# TC377TP_1.net
KiCad netlist of a schematic drawn in Altium Designer
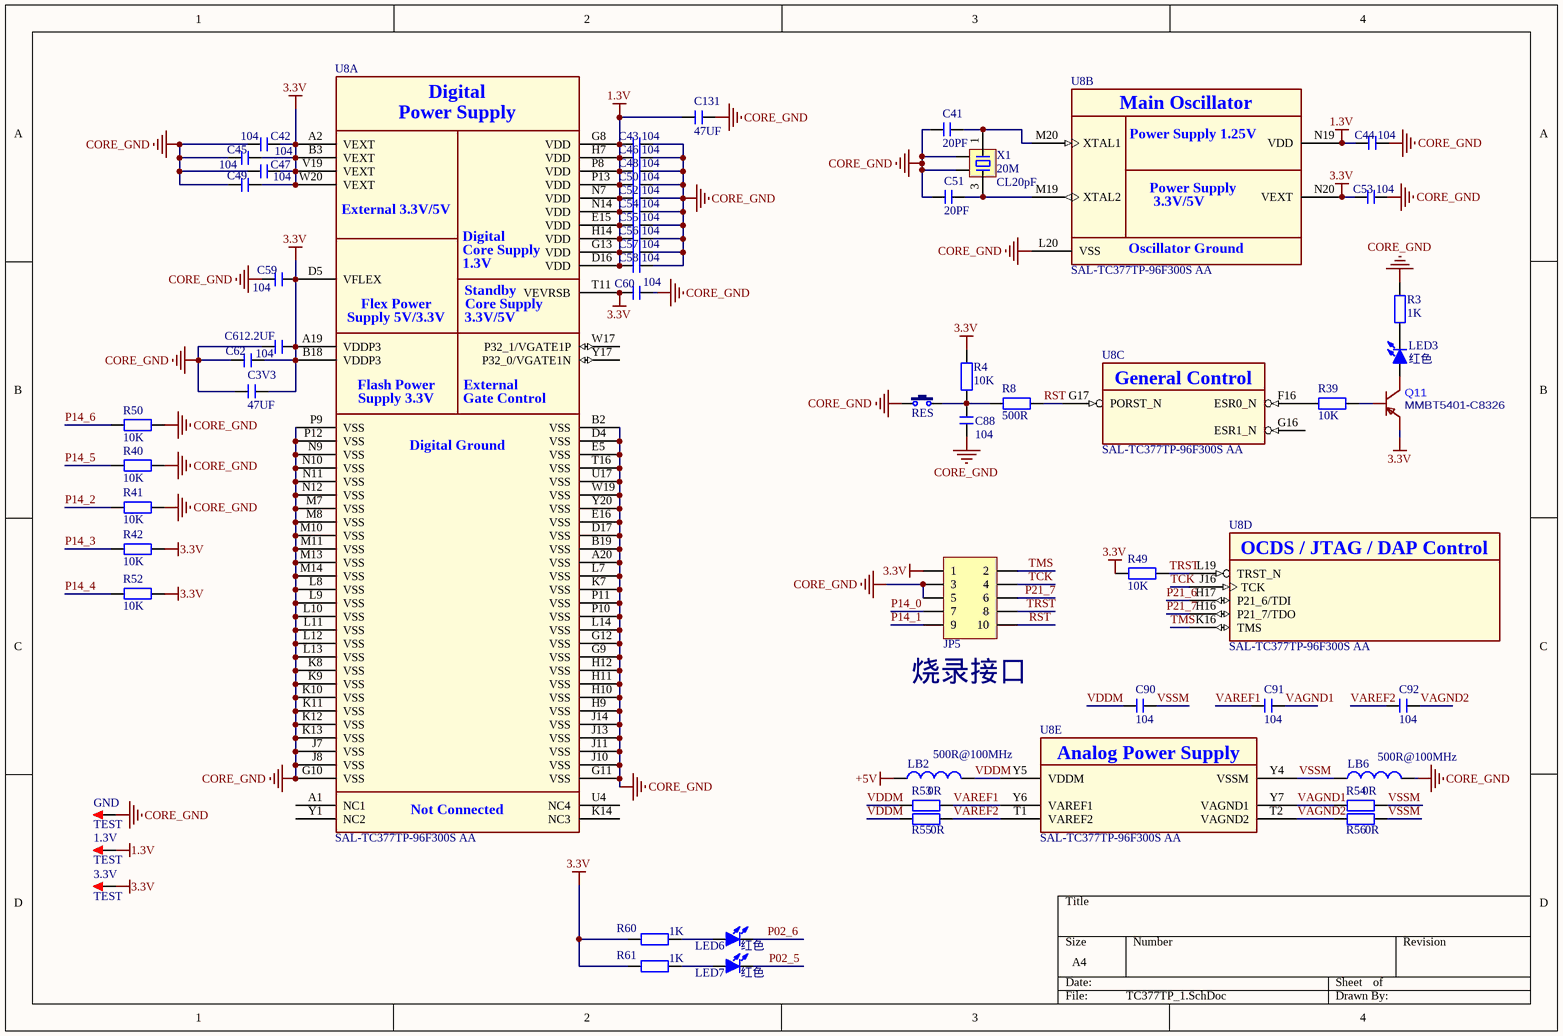
[diagram p0: TC377TP_1.SchDoc]

(export (version "E")
  (design (tool "Eeschema 10.0.6"))
  (components
    (comp (ref "1.3V")
      (value "TEST")
      (footprint "TEST 1.6")
      (description "测试点")
      (fields (field (name "版权归属") "源创客"))
      (libsource (lib "15.1 - 未分类器件") (part "TEST"))
    )
    (comp (ref "3.3V")
      (value "TEST")
      (footprint "TEST 1.6")
      (description "测试点")
      (fields (field (name "版权归属") "源创客"))
      (libsource (lib "15.1 - 未分类器件") (part "TEST"))
    )
    (comp (ref "C3V3")
      (value "47UF")
      (footprint "C 0805_L")
      (description "无极性贴片电容")
      (fields (field (name "版权归属") "源创客"))
      (libsource (lib "3.1   - 电阻-电容-电感") (part "C"))
    )
    (comp (ref "C41")
      (value "20PF")
      (footprint "C 0603_L")
      (description "无极性贴片电容")
      (fields (field (name "版权归属") "源创客"))
      (libsource (lib "3.1   - 电阻-电容-电感") (part "C"))
    )
    (comp (ref "C42")
      (value "104")
      (footprint "C 0603_L")
      (description "无极性贴片电容")
      (fields (field (name "版权归属") "源创客"))
      (libsource (lib "3.1   - 电阻-电容-电感") (part "C"))
    )
    (comp (ref "C43")
      (value "104")
      (footprint "C 0603_L")
      (description "无极性贴片电容")
      (fields (field (name "版权归属") "源创客"))
      (libsource (lib "3.1   - 电阻-电容-电感") (part "C"))
    )
    (comp (ref "C44")
      (value "104")
      (footprint "C 0603_L")
      (description "无极性贴片电容")
      (fields (field (name "版权归属") "源创客"))
      (libsource (lib "3.1   - 电阻-电容-电感") (part "C"))
    )
    (comp (ref "C45")
      (value "104")
      (footprint "C 0603_L")
      (description "无极性贴片电容")
      (fields (field (name "版权归属") "源创客"))
      (libsource (lib "3.1   - 电阻-电容-电感") (part "C"))
    )
    (comp (ref "C46")
      (value "104")
      (footprint "C 0603_L")
      (description "无极性贴片电容")
      (fields (field (name "版权归属") "源创客"))
      (libsource (lib "3.1   - 电阻-电容-电感") (part "C"))
    )
    (comp (ref "C47")
      (value "104")
      (footprint "C 0603_L")
      (description "无极性贴片电容")
      (fields (field (name "版权归属") "源创客"))
      (libsource (lib "3.1   - 电阻-电容-电感") (part "C"))
    )
    (comp (ref "C48")
      (value "104")
      (footprint "C 0603_L")
      (description "无极性贴片电容")
      (fields (field (name "版权归属") "源创客"))
      (libsource (lib "3.1   - 电阻-电容-电感") (part "C"))
    )
    (comp (ref "C49")
      (value "104")
      (footprint "C 0603_L")
      (description "无极性贴片电容")
      (fields (field (name "版权归属") "源创客"))
      (libsource (lib "3.1   - 电阻-电容-电感") (part "C"))
    )
    (comp (ref "C50")
      (value "104")
      (footprint "C 0603_L")
      (description "无极性贴片电容")
      (fields (field (name "版权归属") "源创客"))
      (libsource (lib "3.1   - 电阻-电容-电感") (part "C"))
    )
    (comp (ref "C51")
      (value "20PF")
      (footprint "C 0603_L")
      (description "无极性贴片电容")
      (fields (field (name "版权归属") "源创客"))
      (libsource (lib "3.1   - 电阻-电容-电感") (part "C"))
    )
    (comp (ref "C52")
      (value "104")
      (footprint "C 0603_L")
      (description "无极性贴片电容")
      (fields (field (name "版权归属") "源创客"))
      (libsource (lib "3.1   - 电阻-电容-电感") (part "C"))
    )
    (comp (ref "C53")
      (value "104")
      (footprint "C 0603_L")
      (description "无极性贴片电容")
      (fields (field (name "版权归属") "源创客"))
      (libsource (lib "3.1   - 电阻-电容-电感") (part "C"))
    )
    (comp (ref "C54")
      (value "104")
      (footprint "C 0603_L")
      (description "无极性贴片电容")
      (fields (field (name "版权归属") "源创客"))
      (libsource (lib "3.1   - 电阻-电容-电感") (part "C"))
    )
    (comp (ref "C55")
      (value "104")
      (footprint "C 0603_L")
      (description "无极性贴片电容")
      (fields (field (name "版权归属") "源创客"))
      (libsource (lib "3.1   - 电阻-电容-电感") (part "C"))
    )
    (comp (ref "C56")
      (value "104")
      (footprint "C 0603_L")
      (description "无极性贴片电容")
      (fields (field (name "版权归属") "源创客"))
      (libsource (lib "3.1   - 电阻-电容-电感") (part "C"))
    )
    (comp (ref "C57")
      (value "104")
      (footprint "C 0603_L")
      (description "无极性贴片电容")
      (fields (field (name "版权归属") "源创客"))
      (libsource (lib "3.1   - 电阻-电容-电感") (part "C"))
    )
    (comp (ref "C58")
      (value "104")
      (footprint "C 0603_L")
      (description "无极性贴片电容")
      (fields (field (name "版权归属") "源创客"))
      (libsource (lib "3.1   - 电阻-电容-电感") (part "C"))
    )
    (comp (ref "C59")
      (value "104")
      (footprint "C 0603_L")
      (description "无极性贴片电容")
      (fields (field (name "版权归属") "源创客"))
      (libsource (lib "3.1   - 电阻-电容-电感") (part "C"))
    )
    (comp (ref "C60")
      (value "104")
      (footprint "C 0603_L")
      (description "无极性贴片电容")
      (fields (field (name "版权归属") "源创客"))
      (libsource (lib "3.1   - 电阻-电容-电感") (part "C"))
    )
    (comp (ref "C61")
      (value "2.2UF")
      (footprint "C 0603_L")
      (description "无极性贴片电容")
      (fields (field (name "版权归属") "源创客"))
      (libsource (lib "3.1   - 电阻-电容-电感") (part "C"))
    )
    (comp (ref "C62")
      (value "104")
      (footprint "C 0603_L")
      (description "无极性贴片电容")
      (fields (field (name "版权归属") "源创客"))
      (libsource (lib "3.1   - 电阻-电容-电感") (part "C"))
    )
    (comp (ref "C88")
      (value "104")
      (footprint "C 0603_L")
      (description "无极性贴片电容")
      (fields (field (name "版权归属") "源创客"))
      (libsource (lib "3.1   - 电阻-电容-电感") (part "C"))
    )
    (comp (ref "C90")
      (value "104")
      (footprint "C 0603_L")
      (description "无极性贴片电容")
      (fields (field (name "版权归属") "源创客"))
      (libsource (lib "3.1   - 电阻-电容-电感") (part "C"))
    )
    (comp (ref "C91")
      (value "104")
      (footprint "C 0603_L")
      (description "无极性贴片电容")
      (fields (field (name "版权归属") "源创客"))
      (libsource (lib "3.1   - 电阻-电容-电感") (part "C"))
    )
    (comp (ref "C92")
      (value "104")
      (footprint "C 0603_L")
      (description "无极性贴片电容")
      (fields (field (name "版权归属") "源创客"))
      (libsource (lib "3.1   - 电阻-电容-电感") (part "C"))
    )
    (comp (ref "C131")
      (value "47UF")
      (footprint "C 0805_L")
      (description "无极性贴片电容")
      (fields (field (name "版权归属") "源创客"))
      (libsource (lib "3.1   - 电阻-电容-电感") (part "C"))
    )
    (comp (ref "GND")
      (value "TEST")
      (footprint "TEST 1.6")
      (description "测试点")
      (fields (field (name "版权归属") "源创客"))
      (libsource (lib "15.1 - 未分类器件") (part "TEST"))
    )
    (comp (ref "JP5")
      (value "Header 5X2")
      (footprint "IDC2.54-LI-2x5P")
      (description "5*2P接插件")
      (fields (field (name "版权归属") "源创客"))
      (libsource (lib "4.6   - 接插件-脚距2.54") (part "Header 5X2"))
    )
    (comp (ref "LB2")
      (value "500R@100MHz")
      (footprint "FB 0603_L")
      (description "磁珠")
      (fields (field (name "版权归属") "源创客"))
      (libsource (lib "3.1   - 电阻-电容-电感") (part "LB"))
    )
    (comp (ref "LB6")
      (value "500R@100MHz")
      (footprint "FB 0603_L")
      (description "磁珠")
      (fields (field (name "版权归属") "源创客"))
      (libsource (lib "3.1   - 电阻-电容-电感") (part "LB"))
    )
    (comp (ref "LED3")
      (value "红色")
      (footprint "LED 0603Y")
      (description "贴片LED")
      (fields (field (name "版权归属") "源创客"))
      (libsource (lib "9.1   - LED") (part "LED-SMD"))
    )
    (comp (ref "LED6")
      (value "红色")
      (footprint "LED 0603Y")
      (description "贴片LED")
      (fields (field (name "版权归属") "源创客"))
      (libsource (lib "9.1   - LED") (part "LED-SMD"))
    )
    (comp (ref "LED7")
      (value "红色")
      (footprint "LED 0603Y")
      (description "贴片LED")
      (fields (field (name "版权归属") "源创客"))
      (libsource (lib "9.1   - LED") (part "LED-SMD"))
    )
    (comp (ref "Q11")
      (value "MMBT5401-C8326")
      (footprint "SOT23-3L")
      (libsource (lib "MMBT5401") (part "MMBT5401-C8326"))
    )
    (comp (ref "R3")
      (value "1K")
      (footprint "R 0603_L")
      (description "贴片电阻")
      (fields (field (name "版权归属") "源创客"))
      (libsource (lib "3.1   - 电阻-电容-电感") (part "R"))
    )
    (comp (ref "R4")
      (value "10K")
      (footprint "R 0603_L")
      (description "贴片电阻")
      (fields (field (name "版权归属") "源创客"))
      (libsource (lib "3.1   - 电阻-电容-电感") (part "R"))
    )
    (comp (ref "R8")
      (value "500R")
      (footprint "R 0603_L")
      (description "贴片电阻")
      (fields (field (name "版权归属") "源创客"))
      (libsource (lib "3.1   - 电阻-电容-电感") (part "R"))
    )
    (comp (ref "R39")
      (value "10K")
      (footprint "R 0603_L")
      (description "贴片电阻")
      (fields (field (name "版权归属") "源创客"))
      (libsource (lib "3.1   - 电阻-电容-电感") (part "R"))
    )
    (comp (ref "R40")
      (value "10K")
      (footprint "R 0603_L")
      (description "贴片电阻")
      (fields (field (name "版权归属") "源创客"))
      (libsource (lib "3.1   - 电阻-电容-电感") (part "R"))
    )
    (comp (ref "R41")
      (value "10K")
      (footprint "R 0603_L")
      (description "贴片电阻")
      (fields (field (name "版权归属") "源创客"))
      (libsource (lib "3.1   - 电阻-电容-电感") (part "R"))
    )
    (comp (ref "R42")
      (value "10K")
      (footprint "R 0603_L")
      (description "贴片电阻")
      (fields (field (name "版权归属") "源创客"))
      (libsource (lib "3.1   - 电阻-电容-电感") (part "R"))
    )
    (comp (ref "R49")
      (value "10K")
      (footprint "R 0805_L")
      (description "贴片电阻")
      (fields (field (name "版权归属") "源创客"))
      (libsource (lib "3.1   - 电阻-电容-电感") (part "R"))
    )
    (comp (ref "R50")
      (value "10K")
      (footprint "R 0603_L")
      (description "贴片电阻")
      (fields (field (name "版权归属") "源创客"))
      (libsource (lib "3.1   - 电阻-电容-电感") (part "R"))
    )
    (comp (ref "R52")
      (value "10K")
      (footprint "R 0603_L")
      (description "贴片电阻")
      (fields (field (name "版权归属") "源创客"))
      (libsource (lib "3.1   - 电阻-电容-电感") (part "R"))
    )
    (comp (ref "R53")
      (value "0R")
      (footprint "R 0603_L")
      (description "贴片电阻")
      (fields (field (name "版权归属") "源创客"))
      (libsource (lib "3.1   - 电阻-电容-电感") (part "R"))
    )
    (comp (ref "R54")
      (value "0R")
      (footprint "R 0603_L")
      (description "贴片电阻")
      (fields (field (name "版权归属") "源创客"))
      (libsource (lib "3.1   - 电阻-电容-电感") (part "R"))
    )
    (comp (ref "R55")
      (value "0R")
      (footprint "R 0603_L")
      (description "贴片电阻")
      (fields (field (name "版权归属") "源创客"))
      (libsource (lib "3.1   - 电阻-电容-电感") (part "R"))
    )
    (comp (ref "R56")
      (value "0R")
      (footprint "R 0603_L")
      (description "贴片电阻")
      (fields (field (name "版权归属") "源创客"))
      (libsource (lib "3.1   - 电阻-电容-电感") (part "R"))
    )
    (comp (ref "R60")
      (value "1K")
      (footprint "R 0603_L")
      (description "贴片电阻")
      (fields (field (name "版权归属") "源创客"))
      (libsource (lib "3.1   - 电阻-电容-电感") (part "R"))
    )
    (comp (ref "R61")
      (value "1K")
      (footprint "R 0603_L")
      (description "贴片电阻")
      (fields (field (name "版权归属") "源创客"))
      (libsource (lib "3.1   - 电阻-电容-电感") (part "R"))
    )
    (comp (ref "RES")
      (value "3x6x5")
      (footprint "TSW SMD-3*6*2.5")
      (description "3x6轻触开关")
      (fields (field (name "版权归属") "源创客"))
      (libsource (lib "5.1   - 按键-开关") (part "TSW 3x6"))
    )
    (comp (ref "U8")
      (value "SAL-TC377TP-96F300S AA")
      (footprint "BGA292C80P20X20")
      (description "32-Bit Single-Chip Microcontroller")
      (fields (field (name "MANUFACTURER") "Infineon Technologies"))
      (libsource (lib "SAL-TC377TP-96F300S AA") (part "SAL-TC377TP-96F300S AA"))
    )
    (comp (ref "X1")
      (value "20M")
      (footprint "OSC 3225-4P")
      (description "4脚无源晶振")
      (fields (field (name "负载电容") "CL20pF") (field (name "版权归属") "源创客"))
      (libsource (lib "10.1 - 保险丝-晶振") (part "XTAL-4P"))
    )
  )
  (nets
    (net (code "1") (name "+5V") (class "Default")
      (node (ref "LB2") (pin "1") (pinfunction "1_1") (pintype "passive"))
    )
    (net (code "2") (name "/P02_5") (class "Default")
      (node (ref "LED7") (pin "2") (pinfunction "K_2") (pintype "passive"))
    )
    (net (code "3") (name "/P02_6") (class "Default")
      (node (ref "LED6") (pin "2") (pinfunction "K_2") (pintype "passive"))
    )
    (net (code "4") (name "/P14_0") (class "Default")
      (node (ref "JP5") (pin "7") (pinfunction "7_7") (pintype "passive"))
    )
    (net (code "5") (name "/P14_1") (class "Default")
      (node (ref "JP5") (pin "9") (pinfunction "9_9") (pintype "passive"))
    )
    (net (code "6") (name "/P14_2") (class "Default")
      (node (ref "R41") (pin "1") (pinfunction "1_1") (pintype "passive"))
    )
    (net (code "7") (name "/P14_3") (class "Default")
      (node (ref "R42") (pin "1") (pinfunction "1_1") (pintype "passive"))
    )
    (net (code "8") (name "/P14_4") (class "Default")
      (node (ref "R52") (pin "1") (pinfunction "1_1") (pintype "passive"))
    )
    (net (code "9") (name "/P14_5") (class "Default")
      (node (ref "R40") (pin "1") (pinfunction "1_1") (pintype "passive"))
    )
    (net (code "10") (name "/P14_6") (class "Default")
      (node (ref "R50") (pin "1") (pinfunction "1_1") (pintype "passive"))
    )
    (net (code "11") (name "/P21_6") (class "Default")
      (node (ref "U8") (pin "H17") (pinfunction "P21_6/TDI_H17") (pintype "bidirectional"))
    )
    (net (code "12") (name "/P21_7") (class "Default")
      (node (ref "JP5") (pin "6") (pinfunction "6_6") (pintype "passive"))
      (node (ref "U8") (pin "H16") (pinfunction "P21_7/TDO_H16") (pintype "bidirectional"))
    )
    (net (code "13") (name "/RST") (class "Default")
      (node (ref "JP5") (pin "10") (pinfunction "10_10") (pintype "passive"))
      (node (ref "R8") (pin "2") (pinfunction "2_2") (pintype "passive"))
      (node (ref "U8") (pin "G17") (pinfunction "PORST_N_G17") (pintype "input"))
    )
    (net (code "14") (name "/TCK") (class "Default")
      (node (ref "JP5") (pin "4") (pinfunction "4_4") (pintype "passive"))
      (node (ref "U8") (pin "J16") (pinfunction "TCK_J16") (pintype "input"))
    )
    (net (code "15") (name "/TMS") (class "Default")
      (node (ref "JP5") (pin "2") (pinfunction "2_2") (pintype "passive"))
      (node (ref "U8") (pin "K16") (pinfunction "TMS_K16") (pintype "bidirectional"))
    )
    (net (code "16") (name "/TRST") (class "Default")
      (node (ref "JP5") (pin "8") (pinfunction "8_8") (pintype "passive"))
      (node (ref "R49") (pin "1") (pinfunction "1_1") (pintype "passive"))
      (node (ref "U8") (pin "L19") (pinfunction "TRST_N_L19") (pintype "input"))
    )
    (net (code "17") (name "/VAGND1") (class "Default")
      (node (ref "C91") (pin "1") (pinfunction "1_1") (pintype "passive"))
      (node (ref "R54") (pin "1") (pinfunction "1_1") (pintype "passive"))
      (node (ref "U8") (pin "Y7") (pinfunction "VAGND1_Y7") (pintype "power_in"))
    )
    (net (code "18") (name "/VAGND2") (class "Default")
      (node (ref "C92") (pin "1") (pinfunction "1_1") (pintype "passive"))
      (node (ref "R56") (pin "1") (pinfunction "1_1") (pintype "passive"))
      (node (ref "U8") (pin "T2") (pinfunction "VAGND2_T2") (pintype "power_in"))
    )
    (net (code "19") (name "/VAREF1") (class "Default")
      (node (ref "C91") (pin "2") (pinfunction "2_2") (pintype "passive"))
      (node (ref "R53") (pin "2") (pinfunction "2_2") (pintype "passive"))
      (node (ref "U8") (pin "Y6") (pinfunction "VAREF1_Y6") (pintype "power_in"))
    )
    (net (code "20") (name "/VAREF2") (class "Default")
      (node (ref "C92") (pin "2") (pinfunction "2_2") (pintype "passive"))
      (node (ref "R55") (pin "2") (pinfunction "2_2") (pintype "passive"))
      (node (ref "U8") (pin "T1") (pinfunction "VAREF2_T1") (pintype "power_in"))
    )
    (net (code "21") (name "/VDDM") (class "Default")
      (node (ref "C90") (pin "2") (pinfunction "2_2") (pintype "passive"))
      (node (ref "LB2") (pin "2") (pinfunction "2_2") (pintype "passive"))
      (node (ref "R53") (pin "1") (pinfunction "1_1") (pintype "passive"))
      (node (ref "R55") (pin "1") (pinfunction "1_1") (pintype "passive"))
      (node (ref "U8") (pin "Y5") (pinfunction "VDDM_Y5") (pintype "power_in"))
    )
    (net (code "22") (name "/VSSM") (class "Default")
      (node (ref "C90") (pin "1") (pinfunction "1_1") (pintype "passive"))
      (node (ref "LB6") (pin "1") (pinfunction "1_1") (pintype "passive"))
      (node (ref "R54") (pin "2") (pinfunction "2_2") (pintype "passive"))
      (node (ref "R56") (pin "2") (pinfunction "2_2") (pintype "passive"))
      (node (ref "U8") (pin "Y4") (pinfunction "VSSM_Y4") (pintype "power_in"))
    )
    (net (code "23") (name "1.3V") (class "Default")
      (node (ref "1.3V") (pin "1") (pinfunction "1_1") (pintype "passive"))
      (node (ref "C131") (pin "2") (pinfunction "2_2") (pintype "passive"))
      (node (ref "C43") (pin "2") (pinfunction "2_2") (pintype "passive"))
      (node (ref "C44") (pin "2") (pinfunction "2_2") (pintype "passive"))
      (node (ref "C46") (pin "2") (pinfunction "2_2") (pintype "passive"))
      (node (ref "C48") (pin "2") (pinfunction "2_2") (pintype "passive"))
      (node (ref "C50") (pin "2") (pinfunction "2_2") (pintype "passive"))
      (node (ref "C52") (pin "2") (pinfunction "2_2") (pintype "passive"))
      (node (ref "C54") (pin "2") (pinfunction "2_2") (pintype "passive"))
      (node (ref "C55") (pin "2") (pinfunction "2_2") (pintype "passive"))
      (node (ref "C56") (pin "2") (pinfunction "2_2") (pintype "passive"))
      (node (ref "C57") (pin "2") (pinfunction "2_2") (pintype "passive"))
      (node (ref "C58") (pin "2") (pinfunction "2_2") (pintype "passive"))
      (node (ref "U8") (pin "D16") (pinfunction "VDD_D16") (pintype "power_in"))
      (node (ref "U8") (pin "E15") (pinfunction "VDD_E15") (pintype "power_in"))
      (node (ref "U8") (pin "G13") (pinfunction "VDD_G13") (pintype "power_in"))
      (node (ref "U8") (pin "G8") (pinfunction "VDD_G8") (pintype "power_in"))
      (node (ref "U8") (pin "H14") (pinfunction "VDD_H14") (pintype "power_in"))
      (node (ref "U8") (pin "H7") (pinfunction "VDD_H7") (pintype "power_in"))
      (node (ref "U8") (pin "N14") (pinfunction "VDD_N14") (pintype "power_in"))
      (node (ref "U8") (pin "N19") (pinfunction "VDD_N19") (pintype "power_in"))
      (node (ref "U8") (pin "N7") (pinfunction "VDD_N7") (pintype "power_in"))
      (node (ref "U8") (pin "P13") (pinfunction "VDD_P13") (pintype "power_in"))
      (node (ref "U8") (pin "P8") (pinfunction "VDD_P8") (pintype "power_in"))
    )
    (net (code "24") (name "3.3V") (class "Default")
      (node (ref "3.3V") (pin "1") (pinfunction "1_1") (pintype "passive"))
      (node (ref "C3V3") (pin "2") (pinfunction "2_2") (pintype "passive"))
      (node (ref "C42") (pin "1") (pinfunction "1_1") (pintype "passive"))
      (node (ref "C45") (pin "1") (pinfunction "1_1") (pintype "passive"))
      (node (ref "C47") (pin "1") (pinfunction "1_1") (pintype "passive"))
      (node (ref "C49") (pin "1") (pinfunction "1_1") (pintype "passive"))
      (node (ref "C53") (pin "2") (pinfunction "2_2") (pintype "passive"))
      (node (ref "C59") (pin "1") (pinfunction "1_1") (pintype "passive"))
      (node (ref "C60") (pin "2") (pinfunction "2_2") (pintype "passive"))
      (node (ref "C61") (pin "1") (pinfunction "1_1") (pintype "passive"))
      (node (ref "C62") (pin "1") (pinfunction "1_1") (pintype "passive"))
      (node (ref "JP5") (pin "1") (pinfunction "1_1") (pintype "passive"))
      (node (ref "Q11") (pin "2") (pinfunction "E_2") (pintype "passive"))
      (node (ref "R4") (pin "2") (pinfunction "2_2") (pintype "passive"))
      (node (ref "R42") (pin "2") (pinfunction "2_2") (pintype "passive"))
      (node (ref "R49") (pin "2") (pinfunction "2_2") (pintype "passive"))
      (node (ref "R52") (pin "2") (pinfunction "2_2") (pintype "passive"))
      (node (ref "R60") (pin "2") (pinfunction "2_2") (pintype "passive"))
      (node (ref "R61") (pin "2") (pinfunction "2_2") (pintype "passive"))
      (node (ref "U8") (pin "A19") (pinfunction "VDDP3_A19") (pintype "power_in"))
      (node (ref "U8") (pin "A2") (pinfunction "VEXT_A2") (pintype "power_in"))
      (node (ref "U8") (pin "B18") (pinfunction "VDDP3_B18") (pintype "power_in"))
      (node (ref "U8") (pin "B3") (pinfunction "VEXT_B3") (pintype "power_in"))
      (node (ref "U8") (pin "D5") (pinfunction "VFLEX_D5") (pintype "power_in"))
      (node (ref "U8") (pin "N20") (pinfunction "VEXT_N20") (pintype "power_in"))
      (node (ref "U8") (pin "T11") (pinfunction "VEVRSB_T11") (pintype "power_in"))
      (node (ref "U8") (pin "V19") (pinfunction "VEXT_V19") (pintype "power_in"))
      (node (ref "U8") (pin "W20") (pinfunction "VEXT_W20") (pintype "power_in"))
    )
    (net (code "25") (name "CORE_GND") (class "Default")
      (node (ref "C131") (pin "1") (pinfunction "1_1") (pintype "passive"))
      (node (ref "C3V3") (pin "1") (pinfunction "1_1") (pintype "passive"))
      (node (ref "C41") (pin "2") (pinfunction "2_2") (pintype "passive"))
      (node (ref "C42") (pin "2") (pinfunction "2_2") (pintype "passive"))
      (node (ref "C43") (pin "1") (pinfunction "1_1") (pintype "passive"))
      (node (ref "C44") (pin "1") (pinfunction "1_1") (pintype "passive"))
      (node (ref "C45") (pin "2") (pinfunction "2_2") (pintype "passive"))
      (node (ref "C46") (pin "1") (pinfunction "1_1") (pintype "passive"))
      (node (ref "C47") (pin "2") (pinfunction "2_2") (pintype "passive"))
      (node (ref "C48") (pin "1") (pinfunction "1_1") (pintype "passive"))
      (node (ref "C49") (pin "2") (pinfunction "2_2") (pintype "passive"))
      (node (ref "C50") (pin "1") (pinfunction "1_1") (pintype "passive"))
      (node (ref "C51") (pin "2") (pinfunction "2_2") (pintype "passive"))
      (node (ref "C52") (pin "1") (pinfunction "1_1") (pintype "passive"))
      (node (ref "C53") (pin "1") (pinfunction "1_1") (pintype "passive"))
      (node (ref "C54") (pin "1") (pinfunction "1_1") (pintype "passive"))
      (node (ref "C55") (pin "1") (pinfunction "1_1") (pintype "passive"))
      (node (ref "C56") (pin "1") (pinfunction "1_1") (pintype "passive"))
      (node (ref "C57") (pin "1") (pinfunction "1_1") (pintype "passive"))
      (node (ref "C58") (pin "1") (pinfunction "1_1") (pintype "passive"))
      (node (ref "C59") (pin "2") (pinfunction "2_2") (pintype "passive"))
      (node (ref "C60") (pin "1") (pinfunction "1_1") (pintype "passive"))
      (node (ref "C61") (pin "2") (pinfunction "2_2") (pintype "passive"))
      (node (ref "C62") (pin "2") (pinfunction "2_2") (pintype "passive"))
      (node (ref "C88") (pin "1") (pinfunction "1_1") (pintype "passive"))
      (node (ref "GND") (pin "1") (pinfunction "1_1") (pintype "passive"))
      (node (ref "JP5") (pin "3") (pinfunction "3_3") (pintype "passive"))
      (node (ref "JP5") (pin "5") (pinfunction "5_5") (pintype "passive"))
      (node (ref "LB6") (pin "2") (pinfunction "2_2") (pintype "passive"))
      (node (ref "R3") (pin "1") (pinfunction "1_1") (pintype "passive"))
      (node (ref "R40") (pin "2") (pinfunction "2_2") (pintype "passive"))
      (node (ref "R41") (pin "2") (pinfunction "2_2") (pintype "passive"))
      (node (ref "R50") (pin "2") (pinfunction "2_2") (pintype "passive"))
      (node (ref "RES") (pin "1") (pinfunction "1_1") (pintype "passive"))
      (node (ref "U8") (pin "A20") (pinfunction "VSS_A20") (pintype "power_in"))
      (node (ref "U8") (pin "B19") (pinfunction "VSS_B19") (pintype "power_in"))
      (node (ref "U8") (pin "B2") (pinfunction "VSS_B2") (pintype "power_in"))
      (node (ref "U8") (pin "D17") (pinfunction "VSS_D17") (pintype "power_in"))
      (node (ref "U8") (pin "D4") (pinfunction "VSS_D4") (pintype "power_in"))
      (node (ref "U8") (pin "E16") (pinfunction "VSS_E16") (pintype "power_in"))
      (node (ref "U8") (pin "E5") (pinfunction "VSS_E5") (pintype "power_in"))
      (node (ref "U8") (pin "G10") (pinfunction "VSS_G10") (pintype "power_in"))
      (node (ref "U8") (pin "G11") (pinfunction "VSS_G11") (pintype "power_in"))
      (node (ref "U8") (pin "G12") (pinfunction "VSS_G12") (pintype "power_in"))
      (node (ref "U8") (pin "G9") (pinfunction "VSS_G9") (pintype "power_in"))
      (node (ref "U8") (pin "H10") (pinfunction "VSS_H10") (pintype "power_in"))
      (node (ref "U8") (pin "H11") (pinfunction "VSS_H11") (pintype "power_in"))
      (node (ref "U8") (pin "H12") (pinfunction "VSS_H12") (pintype "power_in"))
      (node (ref "U8") (pin "H9") (pinfunction "VSS_H9") (pintype "power_in"))
      (node (ref "U8") (pin "J10") (pinfunction "VSS_J10") (pintype "power_in"))
      (node (ref "U8") (pin "J11") (pinfunction "VSS_J11") (pintype "power_in"))
      (node (ref "U8") (pin "J13") (pinfunction "VSS_J13") (pintype "power_in"))
      (node (ref "U8") (pin "J14") (pinfunction "VSS_J14") (pintype "power_in"))
      (node (ref "U8") (pin "J7") (pinfunction "VSS_J7") (pintype "power_in"))
      (node (ref "U8") (pin "J8") (pinfunction "VSS_J8") (pintype "power_in"))
      (node (ref "U8") (pin "K10") (pinfunction "VSS_K10") (pintype "power_in"))
      (node (ref "U8") (pin "K11") (pinfunction "VSS_K11") (pintype "power_in"))
      (node (ref "U8") (pin "K12") (pinfunction "VSS_K12") (pintype "power_in"))
      (node (ref "U8") (pin "K13") (pinfunction "VSS_K13") (pintype "power_in"))
      (node (ref "U8") (pin "K7") (pinfunction "VSS_K7") (pintype "power_in"))
      (node (ref "U8") (pin "K8") (pinfunction "VSS_K8") (pintype "power_in"))
      (node (ref "U8") (pin "K9") (pinfunction "VSS_K9") (pintype "power_in"))
      (node (ref "U8") (pin "L10") (pinfunction "VSS_L10") (pintype "power_in"))
      (node (ref "U8") (pin "L11") (pinfunction "VSS_L11") (pintype "power_in"))
      (node (ref "U8") (pin "L12") (pinfunction "VSS_L12") (pintype "power_in"))
      (node (ref "U8") (pin "L13") (pinfunction "VSS_L13") (pintype "power_in"))
      (node (ref "U8") (pin "L14") (pinfunction "VSS_L14") (pintype "power_in"))
      (node (ref "U8") (pin "L20") (pinfunction "VSS_L20") (pintype "power_in"))
      (node (ref "U8") (pin "L7") (pinfunction "VSS_L7") (pintype "power_in"))
      (node (ref "U8") (pin "L8") (pinfunction "VSS_L8") (pintype "power_in"))
      (node (ref "U8") (pin "L9") (pinfunction "VSS_L9") (pintype "power_in"))
      (node (ref "U8") (pin "M10") (pinfunction "VSS_M10") (pintype "power_in"))
      (node (ref "U8") (pin "M11") (pinfunction "VSS_M11") (pintype "power_in"))
      (node (ref "U8") (pin "M13") (pinfunction "VSS_M13") (pintype "power_in"))
      (node (ref "U8") (pin "M14") (pinfunction "VSS_M14") (pintype "power_in"))
      (node (ref "U8") (pin "M7") (pinfunction "VSS_M7") (pintype "power_in"))
      (node (ref "U8") (pin "M8") (pinfunction "VSS_M8") (pintype "power_in"))
      (node (ref "U8") (pin "N10") (pinfunction "VSS_N10") (pintype "power_in"))
      (node (ref "U8") (pin "N11") (pinfunction "VSS_N11") (pintype "power_in"))
      (node (ref "U8") (pin "N12") (pinfunction "VSS_N12") (pintype "power_in"))
      (node (ref "U8") (pin "N9") (pinfunction "VSS_N9") (pintype "power_in"))
      (node (ref "U8") (pin "P10") (pinfunction "VSS_P10") (pintype "power_in"))
      (node (ref "U8") (pin "P11") (pinfunction "VSS_P11") (pintype "power_in"))
      (node (ref "U8") (pin "P12") (pinfunction "VSS_P12") (pintype "power_in"))
      (node (ref "U8") (pin "P9") (pinfunction "VSS_P9") (pintype "power_in"))
      (node (ref "U8") (pin "T16") (pinfunction "VSS_T16") (pintype "power_in"))
      (node (ref "U8") (pin "U17") (pinfunction "VSS_U17") (pintype "power_in"))
      (node (ref "U8") (pin "W19") (pinfunction "VSS_W19") (pintype "power_in"))
      (node (ref "U8") (pin "Y20") (pinfunction "VSS_Y20") (pintype "power_in"))
      (node (ref "X1") (pin "2") (pinfunction "2_2") (pintype "passive"))
      (node (ref "X1") (pin "4") (pinfunction "4_4") (pintype "passive"))
    )
    (net (code "26") (name "Net-(C88-Pad2)") (class "Default")
      (node (ref "C88") (pin "2") (pinfunction "2_2") (pintype "passive"))
      (node (ref "R4") (pin "1") (pinfunction "1_1") (pintype "passive"))
      (node (ref "R8") (pin "1") (pinfunction "1_1") (pintype "passive"))
      (node (ref "RES") (pin "2") (pinfunction "2_2") (pintype "passive"))
    )
    (net (code "27") (name "Net-(LED3-A)") (class "Default")
      (node (ref "LED3") (pin "1") (pinfunction "A_1") (pintype "passive"))
      (node (ref "Q11") (pin "3") (pinfunction "C_3") (pintype "passive"))
    )
    (net (code "28") (name "Net-(LED3-K)") (class "Default")
      (node (ref "LED3") (pin "2") (pinfunction "K_2") (pintype "passive"))
      (node (ref "R3") (pin "2") (pinfunction "2_2") (pintype "passive"))
    )
    (net (code "29") (name "Net-(LED6-A)") (class "Default")
      (node (ref "LED6") (pin "1") (pinfunction "A_1") (pintype "passive"))
      (node (ref "R60") (pin "1") (pinfunction "1_1") (pintype "passive"))
    )
    (net (code "30") (name "Net-(LED7-A)") (class "Default")
      (node (ref "LED7") (pin "1") (pinfunction "A_1") (pintype "passive"))
      (node (ref "R61") (pin "1") (pinfunction "1_1") (pintype "passive"))
    )
    (net (code "31") (name "Net-(Q11-B)") (class "Default")
      (node (ref "Q11") (pin "1") (pinfunction "B_1") (pintype "passive"))
      (node (ref "R39") (pin "1") (pinfunction "1_1") (pintype "passive"))
    )
    (net (code "32") (name "Net-(U8B-XTAL1)") (class "Default")
      (node (ref "C41") (pin "1") (pinfunction "1_1") (pintype "passive"))
      (node (ref "U8") (pin "M20") (pinfunction "XTAL1_M20") (pintype "input"))
      (node (ref "X1") (pin "1") (pinfunction "1_1") (pintype "passive"))
    )
    (net (code "33") (name "Net-(U8B-XTAL2)") (class "Default")
      (node (ref "C51") (pin "1") (pinfunction "1_1") (pintype "passive"))
      (node (ref "U8") (pin "M19") (pinfunction "XTAL2_M19") (pintype "output"))
      (node (ref "X1") (pin "3") (pinfunction "3_3") (pintype "passive"))
    )
    (net (code "34") (name "Net-(U8C-ESR0_N)") (class "Default")
      (node (ref "R39") (pin "2") (pinfunction "2_2") (pintype "passive"))
      (node (ref "U8") (pin "F16") (pinfunction "ESR0_N_F16") (pintype "input"))
    )
    (net (code "35") (name "unconnected-(U8A-NC1-PadA1)") (class "Default")
      (node (ref "U8") (pin "A1") (pinfunction "NC1_A1") (pintype "passive"))
    )
    (net (code "36") (name "unconnected-(U8A-NC2-PadY1)") (class "Default")
      (node (ref "U8") (pin "Y1") (pinfunction "NC2_Y1") (pintype "passive"))
    )
    (net (code "37") (name "unconnected-(U8A-NC3-PadK14)") (class "Default")
      (node (ref "U8") (pin "K14") (pinfunction "NC3_K14") (pintype "passive"))
    )
    (net (code "38") (name "unconnected-(U8A-NC4-PadU4)") (class "Default")
      (node (ref "U8") (pin "U4") (pinfunction "NC4_U4") (pintype "passive"))
    )
    (net (code "39") (name "unconnected-(U8A-P32_0{slash}VGATE1N-PadY17)") (class "Default")
      (node (ref "U8") (pin "Y17") (pinfunction "P32_0/VGATE1N_Y17") (pintype "bidirectional"))
    )
    (net (code "40") (name "unconnected-(U8A-P32_1{slash}VGATE1P-PadW17)") (class "Default")
      (node (ref "U8") (pin "W17") (pinfunction "P32_1/VGATE1P_W17") (pintype "bidirectional"))
    )
    (net (code "41") (name "unconnected-(U8C-ESR1_N-PadG16)") (class "Default")
      (node (ref "U8") (pin "G16") (pinfunction "ESR1_N_G16") (pintype "input"))
    )
  )
)
